# 6to10.net
KiCad netlist of a schematic drawn in EAGLE
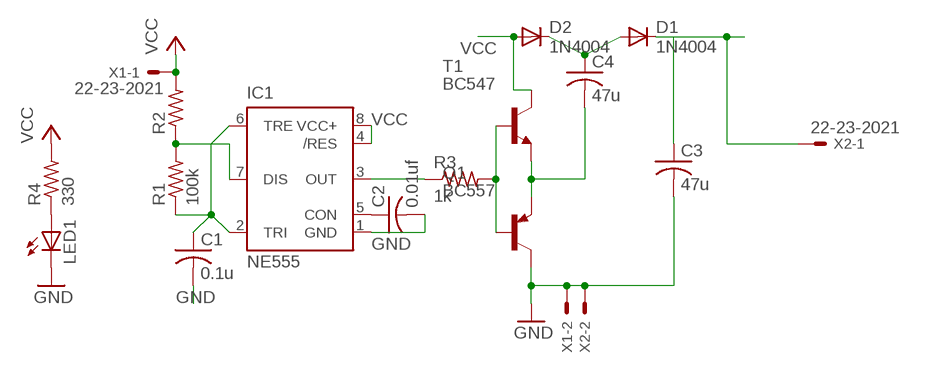
[diagram p0: schematic, sheet 1]

(export (version "E")
  (design (tool "Eeschema 10.0.6"))
  (components
    (comp (ref "C1")
      (value "0.1u")
      (footprint "eagle-import:C050-025X075")
      (libsource (lib "eagle-import") (part "C-US050-025X075"))
    )
    (comp (ref "C2")
      (value "0.01uf")
      (footprint "eagle-import:C050-025X075")
      (libsource (lib "eagle-import") (part "C-US050-025X075"))
    )
    (comp (ref "C3")
      (value "47u")
      (footprint "eagle-import:C050-075X075")
      (libsource (lib "eagle-import") (part "C-US050-075X075"))
    )
    (comp (ref "C4")
      (value "47u")
      (footprint "eagle-import:C050-075X075")
      (libsource (lib "eagle-import") (part "C-US050-075X075"))
    )
    (comp (ref "D1")
      (value "1N4004")
      (footprint "eagle-import:DO41-10")
      (libsource (lib "eagle-import") (part "1N4004"))
    )
    (comp (ref "D2")
      (value "1N4004")
      (footprint "eagle-import:DO41-10")
      (libsource (lib "eagle-import") (part "1N4004"))
    )
    (comp (ref "IC1")
      (value "NE555")
      (footprint "eagle-import:DIL-08")
      (fields (field (name "MF") "Arrow Electronics") (field (name "MPN") "NE555N"))
      (libsource (lib "eagle-import") (part "NE555"))
    )
    (comp (ref "LED1")
      (value "LED5MM")
      (footprint "eagle-import:LED5MM")
      (libsource (lib "eagle-import") (part "LED5MM"))
    )
    (comp (ref "Q1")
      (value "BC557")
      (footprint "eagle-import:TO92")
      (libsource (lib "eagle-import") (part "BC557"))
    )
    (comp (ref "R1")
      (value "100k")
      (footprint "eagle-import:0204_7")
      (libsource (lib "eagle-import") (part "R-US_0204/7"))
    )
    (comp (ref "R2")
      (value "R-US_0204/7")
      (footprint "eagle-import:0204_7")
      (libsource (lib "eagle-import") (part "R-US_0204/7"))
    )
    (comp (ref "R3")
      (value "1k")
      (footprint "eagle-import:0204_7")
      (libsource (lib "eagle-import") (part "R-US_0204/7"))
    )
    (comp (ref "R4")
      (value "330")
      (footprint "eagle-import:0204_7")
      (libsource (lib "eagle-import") (part "R-US_0204/7"))
    )
    (comp (ref "T1")
      (value "BC547")
      (footprint "eagle-import:TO92")
      (libsource (lib "eagle-import") (part "BC547"))
    )
    (comp (ref "X1")
      (value "22-23-2021")
      (footprint "eagle-import:22-23-2021")
      (fields (field (name "MF") "MOLEX"))
      (libsource (lib "eagle-import") (part "22-23-2021"))
    )
    (comp (ref "X2")
      (value "22-23-2021")
      (footprint "eagle-import:22-23-2021")
      (fields (field (name "MF") "MOLEX"))
      (libsource (lib "eagle-import") (part "22-23-2021"))
    )
  )
  (nets
    (net (code "1") (name "GND") (class "Default")
      (node (ref "C1") (pin "2") (pinfunction "2_2") (pintype "passive"))
      (node (ref "C2") (pin "2") (pinfunction "2_2") (pintype "passive"))
      (node (ref "C3") (pin "2") (pinfunction "2_2") (pintype "passive"))
      (node (ref "IC1") (pin "1") (pinfunction "GND_1") (pintype "power_in"))
      (node (ref "LED1") (pin "K") (pinfunction "C_K") (pintype "passive"))
      (node (ref "Q1") (pin "3") (pinfunction "C_3") (pintype "passive"))
      (node (ref "X1") (pin "2") (pinfunction "S_2") (pintype "passive"))
      (node (ref "X2") (pin "2") (pinfunction "S_2") (pintype "passive"))
    )
    (net (code "2") (name "Net-(C4-Pad1)") (class "Default")
      (node (ref "C4") (pin "1") (pinfunction "1_1") (pintype "passive"))
      (node (ref "D1") (pin "A") (pinfunction "A_A") (pintype "passive"))
      (node (ref "D2") (pin "C") (pinfunction "C_C") (pintype "passive"))
    )
    (net (code "3") (name "Net-(IC1-CON)") (class "Default")
      (node (ref "C2") (pin "1") (pinfunction "1_1") (pintype "passive"))
      (node (ref "IC1") (pin "5") (pinfunction "CON_5") (pintype "input"))
    )
    (net (code "4") (name "Net-(IC1-DIS)") (class "Default")
      (node (ref "IC1") (pin "7") (pinfunction "DIS_7") (pintype "input"))
      (node (ref "R1") (pin "2") (pinfunction "2_2") (pintype "passive"))
      (node (ref "R2") (pin "1") (pinfunction "1_1") (pintype "passive"))
    )
    (net (code "5") (name "Net-(IC1-OUT)") (class "Default")
      (node (ref "IC1") (pin "3") (pinfunction "OUT_3") (pintype "output"))
      (node (ref "R3") (pin "1") (pinfunction "1_1") (pintype "passive"))
    )
    (net (code "6") (name "Net-(IC1-TRE)") (class "Default")
      (node (ref "C1") (pin "1") (pinfunction "1_1") (pintype "passive"))
      (node (ref "IC1") (pin "2") (pinfunction "TRI_2") (pintype "input"))
      (node (ref "IC1") (pin "6") (pinfunction "TRE_6") (pintype "input"))
      (node (ref "R1") (pin "1") (pinfunction "1_1") (pintype "passive"))
    )
    (net (code "7") (name "Net-(LED1-PadA)") (class "Default")
      (node (ref "LED1") (pin "A") (pinfunction "A_A") (pintype "passive"))
      (node (ref "R4") (pin "1") (pinfunction "1_1") (pintype "passive"))
    )
    (net (code "8") (name "Net-(Q1-B)") (class "Default")
      (node (ref "Q1") (pin "2") (pinfunction "B_2") (pintype "passive"))
      (node (ref "R3") (pin "2") (pinfunction "2_2") (pintype "passive"))
      (node (ref "T1") (pin "2") (pinfunction "B_2") (pintype "passive"))
    )
    (net (code "9") (name "Net-(Q1-E)") (class "Default")
      (node (ref "C4") (pin "2") (pinfunction "2_2") (pintype "passive"))
      (node (ref "Q1") (pin "1") (pinfunction "E_1") (pintype "passive"))
      (node (ref "T1") (pin "1") (pinfunction "E_1") (pintype "passive"))
    )
    (net (code "10") (name "Net-(X2A-S)") (class "Default")
      (node (ref "C3") (pin "1") (pinfunction "1_1") (pintype "passive"))
      (node (ref "D1") (pin "C") (pinfunction "C_C") (pintype "passive"))
      (node (ref "X2") (pin "1") (pinfunction "S_1") (pintype "passive"))
    )
    (net (code "11") (name "VCC") (class "Default")
      (node (ref "D2") (pin "A") (pinfunction "A_A") (pintype "passive"))
      (node (ref "IC1") (pin "4") (pinfunction "/RES_4") (pintype "input"))
      (node (ref "IC1") (pin "8") (pinfunction "VCC+_8") (pintype "power_in"))
      (node (ref "R2") (pin "2") (pinfunction "2_2") (pintype "passive"))
      (node (ref "R4") (pin "2") (pinfunction "2_2") (pintype "passive"))
      (node (ref "T1") (pin "3") (pinfunction "C_3") (pintype "passive"))
      (node (ref "X1") (pin "1") (pinfunction "S_1") (pintype "passive"))
    )
  )
)
